# 1_lowpass.net
KiCad netlist of a schematic drawn in EAGLE
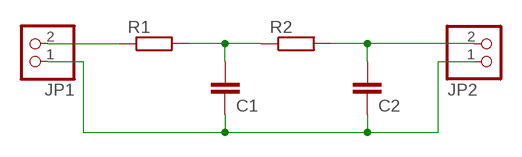
[diagram p0: schematic, sheet 1]

(export (version "E")
  (design (tool "Eeschema 10.0.6"))
  (components
    (comp (ref "C1")
      (value "C-EUC1206")
      (footprint "eagle-import:C1206")
      (libsource (lib "eagle-import") (part "C-EUC1206"))
    )
    (comp (ref "C2")
      (value "C-EUC1206")
      (footprint "eagle-import:C1206")
      (libsource (lib "eagle-import") (part "C-EUC1206"))
    )
    (comp (ref "JP1")
      (value "PINHD-1X2")
      (footprint "eagle-import:1X02")
      (libsource (lib "eagle-import") (part "PINHD-1X2"))
    )
    (comp (ref "JP2")
      (value "PINHD-1X2")
      (footprint "eagle-import:1X02")
      (libsource (lib "eagle-import") (part "PINHD-1X2"))
    )
    (comp (ref "R1")
      (value "R-EU_M1206")
      (footprint "eagle-import:M1206")
      (libsource (lib "eagle-import") (part "R-EU_M1206"))
    )
    (comp (ref "R2")
      (value "R-EU_M1206")
      (footprint "eagle-import:M1206")
      (libsource (lib "eagle-import") (part "R-EU_M1206"))
    )
  )
  (nets
    (net (code "1") (name "Net-(C1-Pad1)") (class "Default")
      (node (ref "C1") (pin "1") (pinfunction "1_1") (pintype "passive"))
      (node (ref "C2") (pin "1") (pinfunction "1_1") (pintype "passive"))
      (node (ref "JP1") (pin "1") (pinfunction "1_1") (pintype "passive"))
      (node (ref "JP2") (pin "1") (pinfunction "1_1") (pintype "passive"))
    )
    (net (code "2") (name "Net-(C1-Pad2)") (class "Default")
      (node (ref "C1") (pin "2") (pinfunction "2_2") (pintype "passive"))
      (node (ref "R1") (pin "2") (pinfunction "2_2") (pintype "passive"))
      (node (ref "R2") (pin "1") (pinfunction "1_1") (pintype "passive"))
    )
    (net (code "3") (name "Net-(C2-Pad2)") (class "Default")
      (node (ref "C2") (pin "2") (pinfunction "2_2") (pintype "passive"))
      (node (ref "JP2") (pin "2") (pinfunction "2_2") (pintype "passive"))
      (node (ref "R2") (pin "2") (pinfunction "2_2") (pintype "passive"))
    )
    (net (code "4") (name "Net-(JP1-Pad2)") (class "Default")
      (node (ref "JP1") (pin "2") (pinfunction "2_2") (pintype "passive"))
      (node (ref "R1") (pin "1") (pinfunction "1_1") (pintype "passive"))
    )
  )
)
